# 6_Interfaces.net
KiCad netlist of a schematic drawn in Altium Designer
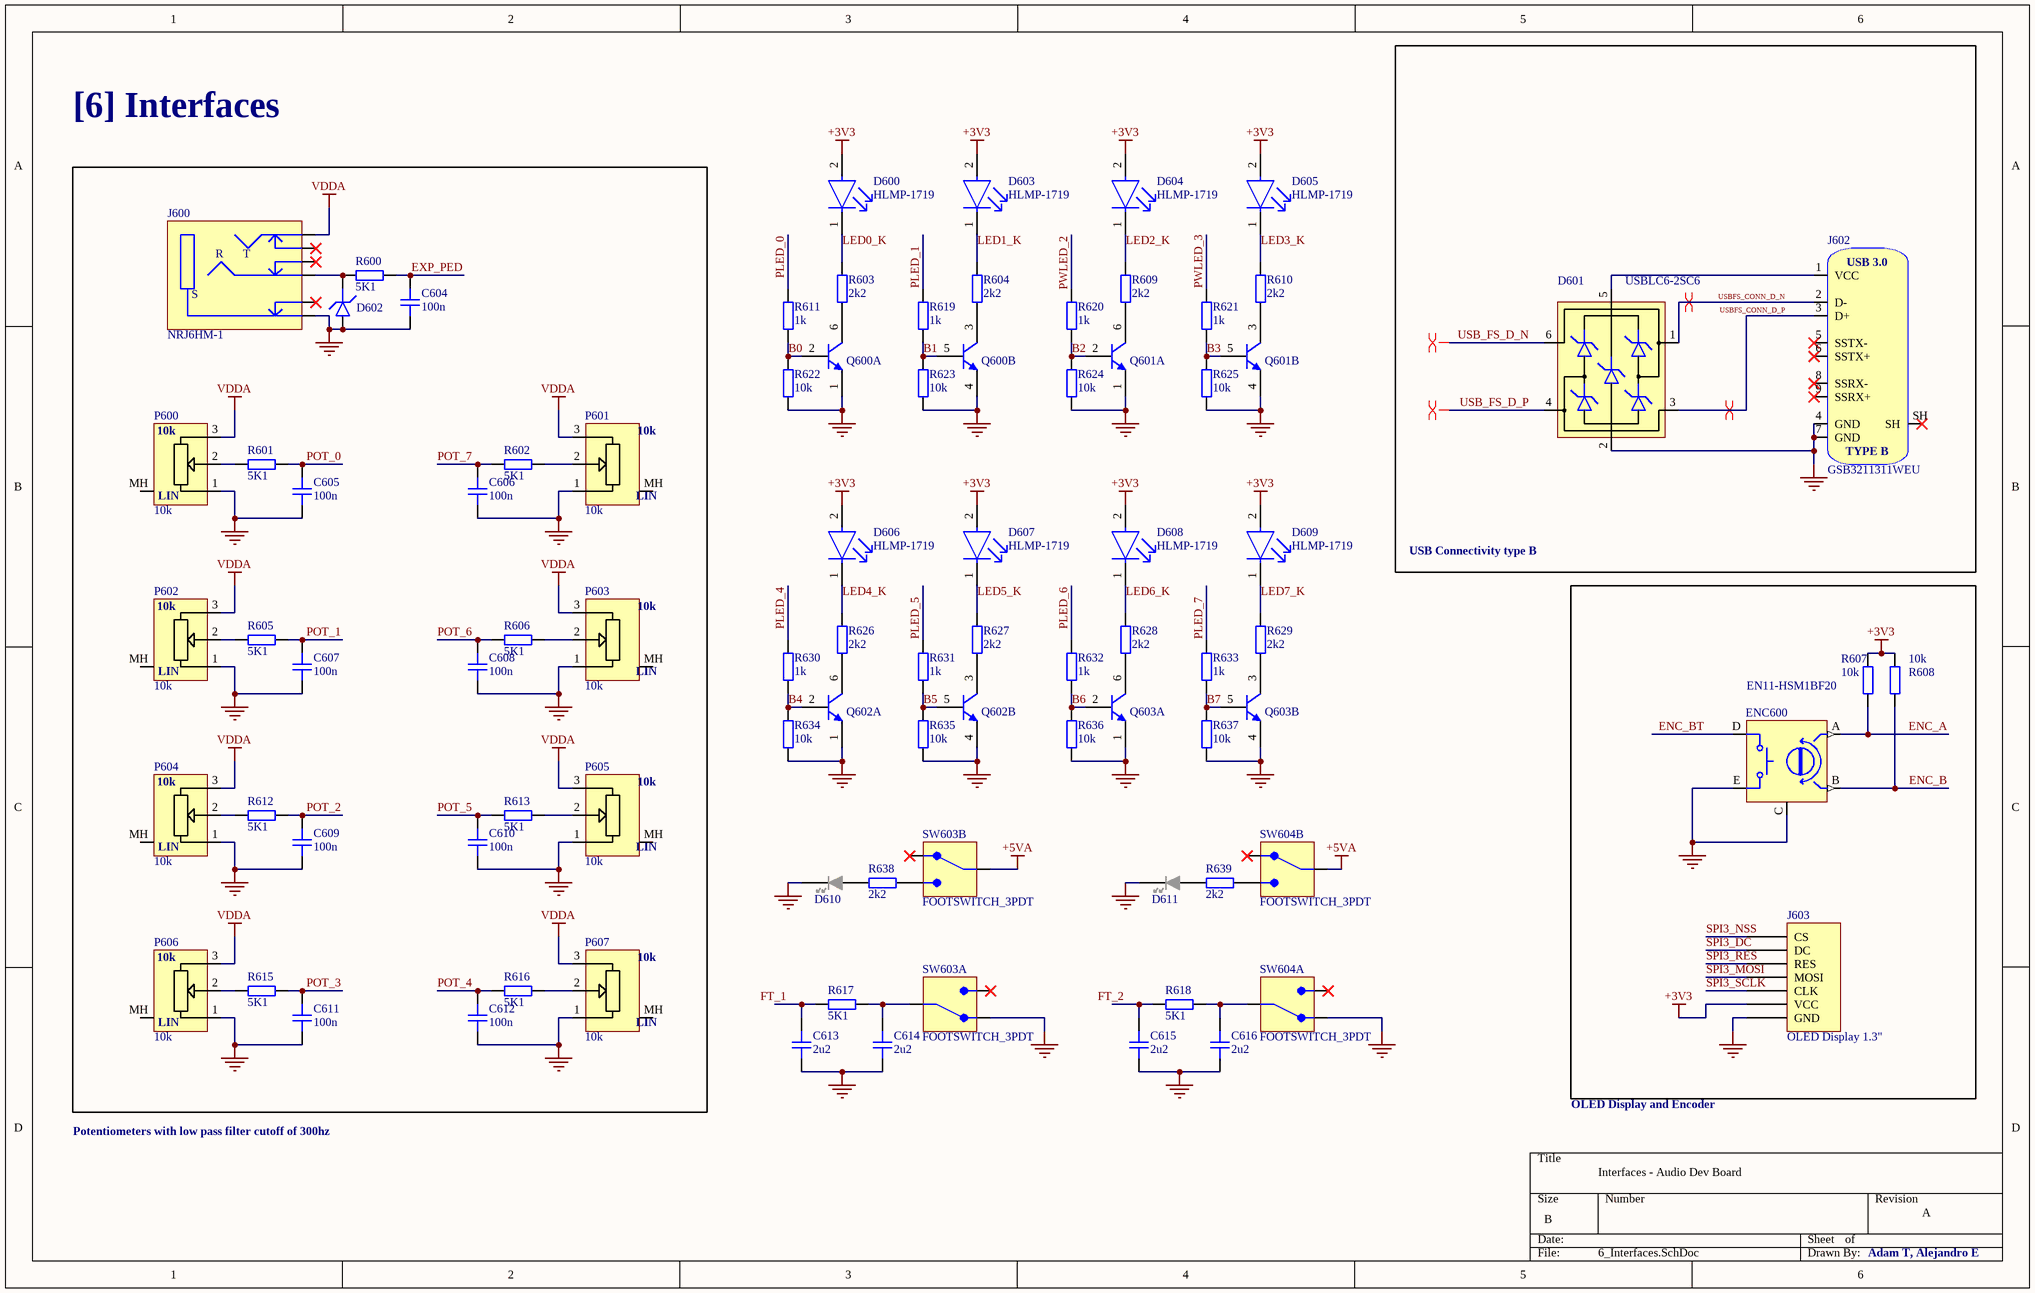
[diagram p0: 6_Interfaces.SchDoc]

(export (version "E")
  (design (tool "Eeschema 10.0.6"))
  (components
    (comp (ref "C604")
      (value "100n")
      (footprint "CAP_0402")
      (description "Capacitor SMD 0402")
      (libsource (lib "Schematic-Lib-PhilsLab") (part "CAP_0402"))
    )
    (comp (ref "C605")
      (value "100n")
      (footprint "CAP_0402")
      (description "Capacitor SMD 0402")
      (libsource (lib "Schematic-Lib-PhilsLab") (part "CAP_0402"))
    )
    (comp (ref "C606")
      (value "100n")
      (footprint "CAP_0402")
      (description "Capacitor SMD 0402")
      (libsource (lib "Schematic-Lib-PhilsLab") (part "CAP_0402"))
    )
    (comp (ref "C607")
      (value "100n")
      (footprint "CAP_0402")
      (description "Capacitor SMD 0402")
      (libsource (lib "Schematic-Lib-PhilsLab") (part "CAP_0402"))
    )
    (comp (ref "C608")
      (value "100n")
      (footprint "CAP_0402")
      (description "Capacitor SMD 0402")
      (libsource (lib "Schematic-Lib-PhilsLab") (part "CAP_0402"))
    )
    (comp (ref "C609")
      (value "100n")
      (footprint "CAP_0402")
      (description "Capacitor SMD 0402")
      (libsource (lib "Schematic-Lib-PhilsLab") (part "CAP_0402"))
    )
    (comp (ref "C610")
      (value "100n")
      (footprint "CAP_0402")
      (description "Capacitor SMD 0402")
      (libsource (lib "Schematic-Lib-PhilsLab") (part "CAP_0402"))
    )
    (comp (ref "C611")
      (value "100n")
      (footprint "CAP_0402")
      (description "Capacitor SMD 0402")
      (libsource (lib "Schematic-Lib-PhilsLab") (part "CAP_0402"))
    )
    (comp (ref "C612")
      (value "100n")
      (footprint "CAP_0402")
      (description "Capacitor SMD 0402")
      (libsource (lib "Schematic-Lib-PhilsLab") (part "CAP_0402"))
    )
    (comp (ref "C613")
      (value "2u2")
      (footprint "CAP_0402")
      (description "Capacitor SMD 0402")
      (libsource (lib "Schematic-Lib-PhilsLab") (part "CAP_0402"))
    )
    (comp (ref "C614")
      (value "2u2")
      (footprint "CAP_0402")
      (description "Capacitor SMD 0402")
      (libsource (lib "Schematic-Lib-PhilsLab") (part "CAP_0402"))
    )
    (comp (ref "C615")
      (value "2u2")
      (footprint "CAP_0402")
      (description "Capacitor SMD 0402")
      (libsource (lib "Schematic-Lib-PhilsLab") (part "CAP_0402"))
    )
    (comp (ref "C616")
      (value "2u2")
      (footprint "CAP_0402")
      (description "Capacitor SMD 0402")
      (libsource (lib "Schematic-Lib-PhilsLab") (part "CAP_0402"))
    )
    (comp (ref "D600")
      (value "HLMP-1719")
      (footprint "FP-HLMP-1719-MFG")
      (description "LED YELLOW DIFFUSED T-1 T/H")
      (fields
        (field (name "MANUFACTURER") "Broadcom")
        (field (name "OCTOPART") "https://octopart.com/hlmp-1719-broadcom-71130405")
      )
      (libsource (lib "Altium Content Vault") (part "8706943c75ba83719d021d2fdc84c58"))
    )
    (comp (ref "D601")
      (value "USBLC6-2SC6")
      (footprint "SOT-23-6")
      (description "Low-Capacitance ESD Protection USB")
      (fields (field (name "MANUFACTURER") "STMicroelectronics"))
      (libsource (lib "Schematic-Lib-PhilsLab") (part "USBLC6-2SC6"))
    )
    (comp (ref "D602")
      (value "CG0402MLU-12G")
      (footprint "D_0402")
      (description "Diode TVS / ESD 0402")
      (libsource (lib "Schematic-Lib-PhilsLab") (part "D_TVS_0402"))
    )
    (comp (ref "D603")
      (value "HLMP-1719")
      (footprint "FP-HLMP-1719-MFG")
      (description "LED YELLOW DIFFUSED T-1 T/H")
      (fields
        (field (name "MANUFACTURER") "Broadcom")
        (field (name "OCTOPART") "https://octopart.com/hlmp-1719-broadcom-71130405")
      )
      (libsource (lib "Altium Content Vault") (part "8706943c75ba83719d021d2fdc84c58"))
    )
    (comp (ref "D604")
      (value "HLMP-1719")
      (footprint "FP-HLMP-1719-MFG")
      (description "LED YELLOW DIFFUSED T-1 T/H")
      (fields
        (field (name "MANUFACTURER") "Broadcom")
        (field (name "OCTOPART") "https://octopart.com/hlmp-1719-broadcom-71130405")
      )
      (libsource (lib "Altium Content Vault") (part "8706943c75ba83719d021d2fdc84c58"))
    )
    (comp (ref "D605")
      (value "HLMP-1719")
      (footprint "FP-HLMP-1719-MFG")
      (description "LED YELLOW DIFFUSED T-1 T/H")
      (fields
        (field (name "MANUFACTURER") "Broadcom")
        (field (name "OCTOPART") "https://octopart.com/hlmp-1719-broadcom-71130405")
      )
      (libsource (lib "Altium Content Vault") (part "8706943c75ba83719d021d2fdc84c58"))
    )
    (comp (ref "D606")
      (value "HLMP-1719")
      (footprint "FP-HLMP-1719-MFG")
      (description "LED YELLOW DIFFUSED T-1 T/H")
      (fields
        (field (name "MANUFACTURER") "Broadcom")
        (field (name "OCTOPART") "https://octopart.com/hlmp-1719-broadcom-71130405")
      )
      (libsource (lib "Altium Content Vault") (part "8706943c75ba83719d021d2fdc84c58"))
    )
    (comp (ref "D607")
      (value "HLMP-1719")
      (footprint "FP-HLMP-1719-MFG")
      (description "LED YELLOW DIFFUSED T-1 T/H")
      (fields
        (field (name "MANUFACTURER") "Broadcom")
        (field (name "OCTOPART") "https://octopart.com/hlmp-1719-broadcom-71130405")
      )
      (libsource (lib "Altium Content Vault") (part "8706943c75ba83719d021d2fdc84c58"))
    )
    (comp (ref "D608")
      (value "HLMP-1719")
      (footprint "FP-HLMP-1719-MFG")
      (description "LED YELLOW DIFFUSED T-1 T/H")
      (fields
        (field (name "MANUFACTURER") "Broadcom")
        (field (name "OCTOPART") "https://octopart.com/hlmp-1719-broadcom-71130405")
      )
      (libsource (lib "Altium Content Vault") (part "8706943c75ba83719d021d2fdc84c58"))
    )
    (comp (ref "D609")
      (value "HLMP-1719")
      (footprint "FP-HLMP-1719-MFG")
      (description "LED YELLOW DIFFUSED T-1 T/H")
      (fields
        (field (name "MANUFACTURER") "Broadcom")
        (field (name "OCTOPART") "https://octopart.com/hlmp-1719-broadcom-71130405")
      )
      (libsource (lib "Altium Content Vault") (part "8706943c75ba83719d021d2fdc84c58"))
    )
    (comp (ref "D610")
      (value "LED")
      (footprint "SLM-530")
      (description "5mm LED Holder Height 17.1mm (w/o LED)")
      (fields (field (name "MANUFACTURER") "BIVAR") (field (name "MANUFACTURER PART NUMBER") "SLM-530"))
      (libsource (lib "Schematic-Lib-PhilsLab") (part "LED_5MM_HOLDER_17MM1"))
    )
    (comp (ref "D611")
      (value "LED")
      (footprint "SLM-530")
      (description "5mm LED Holder Height 17.1mm (w/o LED)")
      (fields (field (name "MANUFACTURER") "BIVAR") (field (name "MANUFACTURER PART NUMBER") "SLM-530"))
      (libsource (lib "Schematic-Lib-PhilsLab") (part "LED_5MM_HOLDER_17MM1"))
    )
    (comp (ref "ENC600")
      (value "EN11-HSM1BF20")
      (footprint "EN11-HSM")
      (description "Rotary Encoder with Switch 20 Detents 7mm Bushing 20mm Threaded Shaft Vertical")
      (fields (field (name "MANUFACTURER") "TT Electronics"))
      (libsource (lib "Schematic-Lib-PhilsLab") (part "EN11-HSM1BF20"))
    )
    (comp (ref "J600")
      (value "NRJ6HM-1")
      (footprint "NRJ6HM-1")
      (description "1/4\" Stereo Jack, TRS Switched")
      (fields (field (name "MANUFACTURER") "Neutrik"))
      (libsource (lib "Schematic-Lib-PhilsLab") (part "NRJ6HM-1"))
    )
    (comp (ref "J602")
      (value "GSB3211311WEU")
      (footprint "GSB3211311WEU")
      (description "USB Connector Type B 3.0 Through-Hole")
      (fields (field (name "MANUFACTURER") "Amphenol"))
      (libsource (lib "Schematic-Lib-PhilsLab") (part "GSB3211311WEU"))
    )
    (comp (ref "J603")
      (value "OLED Display 1.3\"")
      (footprint "OLED Display: 128x64, 1.3\",")
      (description "Poulolu OLED Display: 128x64, 1.3\",")
      (libsource (lib "Schematic-Lib-PhilsLab") (part "OLED Display{colon} 128x64, 1.3{dblquote},"))
    )
    (comp (ref "P600")
      (value "10k")
      (footprint "P0915N-EC15BR10K")
      (description "Potentiometer Vertical 10k Linear Taper THT PCB-Mount Smooth Shaft w/ Slot D=6mm L=15mm")
      (fields
        (field (name "MANUFACTURER") "TT Electronics")
        (field (name "MANUFACTURER PART NUMBER") "P0915N-EC15BR10K")
      )
      (libsource (lib "Schematic-Lib-PhilsLab") (part "P0915N-EC15BR10K"))
    )
    (comp (ref "P601")
      (value "10k")
      (footprint "P0915N-EC15BR10K")
      (description "Potentiometer Vertical 10k Linear Taper THT PCB-Mount Smooth Shaft w/ Slot D=6mm L=15mm")
      (fields
        (field (name "MANUFACTURER") "TT Electronics")
        (field (name "MANUFACTURER PART NUMBER") "P0915N-EC15BR10K")
      )
      (libsource (lib "") (part "P0915N-EC15BR10K_1"))
    )
    (comp (ref "P602")
      (value "10k")
      (footprint "P0915N-EC15BR10K")
      (description "Potentiometer Vertical 10k Linear Taper THT PCB-Mount Smooth Shaft w/ Slot D=6mm L=15mm")
      (fields
        (field (name "MANUFACTURER") "TT Electronics")
        (field (name "MANUFACTURER PART NUMBER") "P0915N-EC15BR10K")
      )
      (libsource (lib "Schematic-Lib-PhilsLab") (part "P0915N-EC15BR10K"))
    )
    (comp (ref "P603")
      (value "10k")
      (footprint "P0915N-EC15BR10K")
      (description "Potentiometer Vertical 10k Linear Taper THT PCB-Mount Smooth Shaft w/ Slot D=6mm L=15mm")
      (fields
        (field (name "MANUFACTURER") "TT Electronics")
        (field (name "MANUFACTURER PART NUMBER") "P0915N-EC15BR10K")
      )
      (libsource (lib "") (part "P0915N-EC15BR10K_1"))
    )
    (comp (ref "P604")
      (value "10k")
      (footprint "P0915N-EC15BR10K")
      (description "Potentiometer Vertical 10k Linear Taper THT PCB-Mount Smooth Shaft w/ Slot D=6mm L=15mm")
      (fields
        (field (name "MANUFACTURER") "TT Electronics")
        (field (name "MANUFACTURER PART NUMBER") "P0915N-EC15BR10K")
      )
      (libsource (lib "Schematic-Lib-PhilsLab") (part "P0915N-EC15BR10K"))
    )
    (comp (ref "P605")
      (value "10k")
      (footprint "P0915N-EC15BR10K")
      (description "Potentiometer Vertical 10k Linear Taper THT PCB-Mount Smooth Shaft w/ Slot D=6mm L=15mm")
      (fields
        (field (name "MANUFACTURER") "TT Electronics")
        (field (name "MANUFACTURER PART NUMBER") "P0915N-EC15BR10K")
      )
      (libsource (lib "") (part "P0915N-EC15BR10K_1"))
    )
    (comp (ref "P606")
      (value "10k")
      (footprint "P0915N-EC15BR10K")
      (description "Potentiometer Vertical 10k Linear Taper THT PCB-Mount Smooth Shaft w/ Slot D=6mm L=15mm")
      (fields
        (field (name "MANUFACTURER") "TT Electronics")
        (field (name "MANUFACTURER PART NUMBER") "P0915N-EC15BR10K")
      )
      (libsource (lib "Schematic-Lib-PhilsLab") (part "P0915N-EC15BR10K"))
    )
    (comp (ref "P607")
      (value "10k")
      (footprint "P0915N-EC15BR10K")
      (description "Potentiometer Vertical 10k Linear Taper THT PCB-Mount Smooth Shaft w/ Slot D=6mm L=15mm")
      (fields
        (field (name "MANUFACTURER") "TT Electronics")
        (field (name "MANUFACTURER PART NUMBER") "P0915N-EC15BR10K")
      )
      (libsource (lib "") (part "P0915N-EC15BR10K_1"))
    )
    (comp (ref "Q600")
      (value "MBT3904DW1T1G")
      (footprint "ONSC-SOT-363-6-419B-02_W_V")
      (description "Dual General Purpose Transistors, 6-Pin SOT-363, Pb-Free, Tape and Reel")
      (fields (field (name "MANUFACTURER") "On Semiconductor"))
      (libsource (lib "Altium Content Vault") (part "ONSC-NPN_NPN-6_F"))
    )
    (comp (ref "Q601")
      (value "MBT3904DW1T1G")
      (footprint "ONSC-SOT-363-6-419B-02_W_V")
      (description "Dual General Purpose Transistors, 6-Pin SOT-363, Pb-Free, Tape and Reel")
      (fields (field (name "MANUFACTURER") "On Semiconductor"))
      (libsource (lib "Altium Content Vault") (part "ONSC-NPN_NPN-6_F"))
    )
    (comp (ref "Q602")
      (value "MBT3904DW1T1G")
      (footprint "ONSC-SOT-363-6-419B-02_W_V")
      (description "Dual General Purpose Transistors, 6-Pin SOT-363, Pb-Free, Tape and Reel")
      (fields (field (name "MANUFACTURER") "On Semiconductor"))
      (libsource (lib "Altium Content Vault") (part "ONSC-NPN_NPN-6_F"))
    )
    (comp (ref "Q603")
      (value "MBT3904DW1T1G")
      (footprint "ONSC-SOT-363-6-419B-02_W_V")
      (description "Dual General Purpose Transistors, 6-Pin SOT-363, Pb-Free, Tape and Reel")
      (fields (field (name "MANUFACTURER") "On Semiconductor"))
      (libsource (lib "Altium Content Vault") (part "ONSC-NPN_NPN-6_F"))
    )
    (comp (ref "R600")
      (value "5K1")
      (footprint "RES_0402")
      (description "Resistor SMD 0402")
      (libsource (lib "Schematic-Lib-PhilsLab") (part "RES_0402"))
    )
    (comp (ref "R601")
      (value "5K1")
      (footprint "RES_0402")
      (description "Resistor SMD 0402")
      (libsource (lib "Schematic-Lib-PhilsLab") (part "RES_0402"))
    )
    (comp (ref "R602")
      (value "5K1")
      (footprint "RES_0402")
      (description "Resistor SMD 0402")
      (libsource (lib "Schematic-Lib-PhilsLab") (part "RES_0402"))
    )
    (comp (ref "R603")
      (value "2k2")
      (footprint "RES_0402")
      (description "Resistor SMD 0402")
      (libsource (lib "Schematic-Lib-PhilsLab") (part "RES_0402"))
    )
    (comp (ref "R604")
      (value "2k2")
      (footprint "RES_0402")
      (description "Resistor SMD 0402")
      (libsource (lib "Schematic-Lib-PhilsLab") (part "RES_0402"))
    )
    (comp (ref "R605")
      (value "5K1")
      (footprint "RES_0402")
      (description "Resistor SMD 0402")
      (libsource (lib "Schematic-Lib-PhilsLab") (part "RES_0402"))
    )
    (comp (ref "R606")
      (value "5K1")
      (footprint "RES_0402")
      (description "Resistor SMD 0402")
      (libsource (lib "Schematic-Lib-PhilsLab") (part "RES_0402"))
    )
    (comp (ref "R607")
      (value "10k")
      (footprint "RES_0402")
      (description "Resistor SMD 0402")
      (libsource (lib "Schematic-Lib-PhilsLab") (part "RES_0402"))
    )
    (comp (ref "R608")
      (value "10k")
      (footprint "RES_0402")
      (description "Resistor SMD 0402")
      (libsource (lib "Schematic-Lib-PhilsLab") (part "RES_0402"))
    )
    (comp (ref "R609")
      (value "2k2")
      (footprint "RES_0402")
      (description "Resistor SMD 0402")
      (libsource (lib "Schematic-Lib-PhilsLab") (part "RES_0402"))
    )
    (comp (ref "R610")
      (value "2k2")
      (footprint "RES_0402")
      (description "Resistor SMD 0402")
      (libsource (lib "Schematic-Lib-PhilsLab") (part "RES_0402"))
    )
    (comp (ref "R611")
      (value "1k")
      (footprint "RES_0402")
      (description "Resistor SMD 0402")
      (libsource (lib "Schematic-Lib-PhilsLab") (part "RES_0402"))
    )
    (comp (ref "R612")
      (value "5K1")
      (footprint "RES_0402")
      (description "Resistor SMD 0402")
      (libsource (lib "Schematic-Lib-PhilsLab") (part "RES_0402"))
    )
    (comp (ref "R613")
      (value "5K1")
      (footprint "RES_0402")
      (description "Resistor SMD 0402")
      (libsource (lib "Schematic-Lib-PhilsLab") (part "RES_0402"))
    )
    (comp (ref "R615")
      (value "5K1")
      (footprint "RES_0402")
      (description "Resistor SMD 0402")
      (libsource (lib "Schematic-Lib-PhilsLab") (part "RES_0402"))
    )
    (comp (ref "R616")
      (value "5K1")
      (footprint "RES_0402")
      (description "Resistor SMD 0402")
      (libsource (lib "Schematic-Lib-PhilsLab") (part "RES_0402"))
    )
    (comp (ref "R617")
      (value "5K1")
      (footprint "RES_0402")
      (description "Resistor SMD 0402")
      (libsource (lib "Schematic-Lib-PhilsLab") (part "RES_0402"))
    )
    (comp (ref "R618")
      (value "5K1")
      (footprint "RES_0402")
      (description "Resistor SMD 0402")
      (libsource (lib "Schematic-Lib-PhilsLab") (part "RES_0402"))
    )
    (comp (ref "R619")
      (value "1k")
      (footprint "RES_0402")
      (description "Resistor SMD 0402")
      (libsource (lib "Schematic-Lib-PhilsLab") (part "RES_0402"))
    )
    (comp (ref "R620")
      (value "1k")
      (footprint "RES_0402")
      (description "Resistor SMD 0402")
      (libsource (lib "Schematic-Lib-PhilsLab") (part "RES_0402"))
    )
    (comp (ref "R621")
      (value "1k")
      (footprint "RES_0402")
      (description "Resistor SMD 0402")
      (libsource (lib "Schematic-Lib-PhilsLab") (part "RES_0402"))
    )
    (comp (ref "R622")
      (value "10k")
      (footprint "RES_0402")
      (description "Resistor SMD 0402")
      (libsource (lib "Schematic-Lib-PhilsLab") (part "RES_0402"))
    )
    (comp (ref "R623")
      (value "10k")
      (footprint "RES_0402")
      (description "Resistor SMD 0402")
      (libsource (lib "Schematic-Lib-PhilsLab") (part "RES_0402"))
    )
    (comp (ref "R624")
      (value "10k")
      (footprint "RES_0402")
      (description "Resistor SMD 0402")
      (libsource (lib "Schematic-Lib-PhilsLab") (part "RES_0402"))
    )
    (comp (ref "R625")
      (value "10k")
      (footprint "RES_0402")
      (description "Resistor SMD 0402")
      (libsource (lib "Schematic-Lib-PhilsLab") (part "RES_0402"))
    )
    (comp (ref "R626")
      (value "2k2")
      (footprint "RES_0402")
      (description "Resistor SMD 0402")
      (libsource (lib "Schematic-Lib-PhilsLab") (part "RES_0402"))
    )
    (comp (ref "R627")
      (value "2k2")
      (footprint "RES_0402")
      (description "Resistor SMD 0402")
      (libsource (lib "Schematic-Lib-PhilsLab") (part "RES_0402"))
    )
    (comp (ref "R628")
      (value "2k2")
      (footprint "RES_0402")
      (description "Resistor SMD 0402")
      (libsource (lib "Schematic-Lib-PhilsLab") (part "RES_0402"))
    )
    (comp (ref "R629")
      (value "2k2")
      (footprint "RES_0402")
      (description "Resistor SMD 0402")
      (libsource (lib "Schematic-Lib-PhilsLab") (part "RES_0402"))
    )
    (comp (ref "R630")
      (value "1k")
      (footprint "RES_0402")
      (description "Resistor SMD 0402")
      (libsource (lib "Schematic-Lib-PhilsLab") (part "RES_0402"))
    )
    (comp (ref "R631")
      (value "1k")
      (footprint "RES_0402")
      (description "Resistor SMD 0402")
      (libsource (lib "Schematic-Lib-PhilsLab") (part "RES_0402"))
    )
    (comp (ref "R632")
      (value "1k")
      (footprint "RES_0402")
      (description "Resistor SMD 0402")
      (libsource (lib "Schematic-Lib-PhilsLab") (part "RES_0402"))
    )
    (comp (ref "R633")
      (value "1k")
      (footprint "RES_0402")
      (description "Resistor SMD 0402")
      (libsource (lib "Schematic-Lib-PhilsLab") (part "RES_0402"))
    )
    (comp (ref "R634")
      (value "10k")
      (footprint "RES_0402")
      (description "Resistor SMD 0402")
      (libsource (lib "Schematic-Lib-PhilsLab") (part "RES_0402"))
    )
    (comp (ref "R635")
      (value "10k")
      (footprint "RES_0402")
      (description "Resistor SMD 0402")
      (libsource (lib "Schematic-Lib-PhilsLab") (part "RES_0402"))
    )
    (comp (ref "R636")
      (value "10k")
      (footprint "RES_0402")
      (description "Resistor SMD 0402")
      (libsource (lib "Schematic-Lib-PhilsLab") (part "RES_0402"))
    )
    (comp (ref "R637")
      (value "10k")
      (footprint "RES_0402")
      (description "Resistor SMD 0402")
      (libsource (lib "Schematic-Lib-PhilsLab") (part "RES_0402"))
    )
    (comp (ref "R638")
      (value "2k2")
      (footprint "RES_0402")
      (description "Resistor SMD 0402")
      (libsource (lib "Schematic-Lib-PhilsLab") (part "RES_0402"))
    )
    (comp (ref "R639")
      (value "2k2")
      (footprint "RES_0402")
      (description "Resistor SMD 0402")
      (libsource (lib "Schematic-Lib-PhilsLab") (part "RES_0402"))
    )
    (comp (ref "SW603")
      (value "FOOTSWITCH_3PDT")
      (footprint "FOOTSWITCH_3PDT")
      (description "Generic 3PDT Footswitch")
      (libsource (lib "") (part "FOOTSWITCH_3PDT_1"))
    )
    (comp (ref "SW604")
      (value "FOOTSWITCH_3PDT")
      (footprint "FOOTSWITCH_3PDT")
      (description "Generic 3PDT Footswitch")
      (libsource (lib "") (part "FOOTSWITCH_3PDT_1"))
    )
  )
  (nets
    (net (code "1") (name "+3V3") (class "Default")
      (node (ref "D600") (pin "2") (pinfunction "A_2") (pintype "passive"))
      (node (ref "D603") (pin "2") (pinfunction "A_2") (pintype "passive"))
      (node (ref "D604") (pin "2") (pinfunction "A_2") (pintype "passive"))
      (node (ref "D605") (pin "2") (pinfunction "A_2") (pintype "passive"))
      (node (ref "D606") (pin "2") (pinfunction "A_2") (pintype "passive"))
      (node (ref "D607") (pin "2") (pinfunction "A_2") (pintype "passive"))
      (node (ref "D608") (pin "2") (pinfunction "A_2") (pintype "passive"))
      (node (ref "D609") (pin "2") (pinfunction "A_2") (pintype "passive"))
      (node (ref "J603") (pin "VCC") (pinfunction "VCC_VCC") (pintype "passive"))
      (node (ref "R607") (pin "2") (pinfunction "2_2") (pintype "passive"))
      (node (ref "R608") (pin "2") (pinfunction "2_2") (pintype "passive"))
    )
    (net (code "2") (name "+5VA") (class "Default")
      (node (ref "SW603") (pin "COM2") (pinfunction "COM2_COM2") (pintype "passive"))
      (node (ref "SW604") (pin "COM2") (pinfunction "COM2_COM2") (pintype "passive"))
    )
    (net (code "3") (name "/B0") (class "Default")
      (node (ref "Q600") (pin "2") (pinfunction "B_2") (pintype "passive"))
      (node (ref "R611") (pin "1") (pinfunction "1_1") (pintype "passive"))
      (node (ref "R622") (pin "2") (pinfunction "2_2") (pintype "passive"))
    )
    (net (code "4") (name "/B1") (class "Default")
      (node (ref "Q600") (pin "5") (pinfunction "B_5") (pintype "passive"))
      (node (ref "R619") (pin "1") (pinfunction "1_1") (pintype "passive"))
      (node (ref "R623") (pin "2") (pinfunction "2_2") (pintype "passive"))
    )
    (net (code "5") (name "/B2") (class "Default")
      (node (ref "Q601") (pin "2") (pinfunction "B_2") (pintype "passive"))
      (node (ref "R620") (pin "1") (pinfunction "1_1") (pintype "passive"))
      (node (ref "R624") (pin "2") (pinfunction "2_2") (pintype "passive"))
    )
    (net (code "6") (name "/B3") (class "Default")
      (node (ref "Q601") (pin "5") (pinfunction "B_5") (pintype "passive"))
      (node (ref "R621") (pin "1") (pinfunction "1_1") (pintype "passive"))
      (node (ref "R625") (pin "2") (pinfunction "2_2") (pintype "passive"))
    )
    (net (code "7") (name "/B4") (class "Default")
      (node (ref "Q602") (pin "2") (pinfunction "B_2") (pintype "passive"))
      (node (ref "R630") (pin "1") (pinfunction "1_1") (pintype "passive"))
      (node (ref "R634") (pin "2") (pinfunction "2_2") (pintype "passive"))
    )
    (net (code "8") (name "/B5") (class "Default")
      (node (ref "Q602") (pin "5") (pinfunction "B_5") (pintype "passive"))
      (node (ref "R631") (pin "1") (pinfunction "1_1") (pintype "passive"))
      (node (ref "R635") (pin "2") (pinfunction "2_2") (pintype "passive"))
    )
    (net (code "9") (name "/B6") (class "Default")
      (node (ref "Q603") (pin "2") (pinfunction "B_2") (pintype "passive"))
      (node (ref "R632") (pin "1") (pinfunction "1_1") (pintype "passive"))
      (node (ref "R636") (pin "2") (pinfunction "2_2") (pintype "passive"))
    )
    (net (code "10") (name "/B7") (class "Default")
      (node (ref "Q603") (pin "5") (pinfunction "B_5") (pintype "passive"))
      (node (ref "R633") (pin "1") (pinfunction "1_1") (pintype "passive"))
      (node (ref "R637") (pin "2") (pinfunction "2_2") (pintype "passive"))
    )
    (net (code "11") (name "/ENC_A") (class "Default")
      (node (ref "ENC600") (pin "A") (pinfunction "A_A") (pintype "output"))
      (node (ref "R607") (pin "1") (pinfunction "1_1") (pintype "passive"))
    )
    (net (code "12") (name "/ENC_B") (class "Default")
      (node (ref "ENC600") (pin "B") (pinfunction "B_B") (pintype "output"))
      (node (ref "R608") (pin "1") (pinfunction "1_1") (pintype "passive"))
    )
    (net (code "13") (name "/ENC_BT") (class "Default")
      (node (ref "ENC600") (pin "D") (pinfunction "D_D") (pintype "passive"))
    )
    (net (code "14") (name "/EXP_PED") (class "Default")
      (node (ref "C604") (pin "2") (pinfunction "2_2") (pintype "passive"))
      (node (ref "R600") (pin "2") (pinfunction "2_2") (pintype "passive"))
    )
    (net (code "15") (name "/FT_1") (class "Default")
      (node (ref "C613") (pin "2") (pinfunction "2_2") (pintype "passive"))
      (node (ref "R617") (pin "1") (pinfunction "1_1") (pintype "passive"))
    )
    (net (code "16") (name "/FT_2") (class "Default")
      (node (ref "C615") (pin "2") (pinfunction "2_2") (pintype "passive"))
      (node (ref "R618") (pin "1") (pinfunction "1_1") (pintype "passive"))
    )
    (net (code "17") (name "/LED0_K") (class "Default")
      (node (ref "D600") (pin "1") (pinfunction "C_1") (pintype "passive"))
      (node (ref "R603") (pin "2") (pinfunction "2_2") (pintype "passive"))
    )
    (net (code "18") (name "/LED1_K") (class "Default")
      (node (ref "D603") (pin "1") (pinfunction "C_1") (pintype "passive"))
      (node (ref "R604") (pin "2") (pinfunction "2_2") (pintype "passive"))
    )
    (net (code "19") (name "/LED2_K") (class "Default")
      (node (ref "D604") (pin "1") (pinfunction "C_1") (pintype "passive"))
      (node (ref "R609") (pin "2") (pinfunction "2_2") (pintype "passive"))
    )
    (net (code "20") (name "/LED3_K") (class "Default")
      (node (ref "D605") (pin "1") (pinfunction "C_1") (pintype "passive"))
      (node (ref "R610") (pin "2") (pinfunction "2_2") (pintype "passive"))
    )
    (net (code "21") (name "/LED4_K") (class "Default")
      (node (ref "D606") (pin "1") (pinfunction "C_1") (pintype "passive"))
      (node (ref "R626") (pin "2") (pinfunction "2_2") (pintype "passive"))
    )
    (net (code "22") (name "/LED5_K") (class "Default")
      (node (ref "D607") (pin "1") (pinfunction "C_1") (pintype "passive"))
      (node (ref "R627") (pin "2") (pinfunction "2_2") (pintype "passive"))
    )
    (net (code "23") (name "/LED6_K") (class "Default")
      (node (ref "D608") (pin "1") (pinfunction "C_1") (pintype "passive"))
      (node (ref "R628") (pin "2") (pinfunction "2_2") (pintype "passive"))
    )
    (net (code "24") (name "/LED7_K") (class "Default")
      (node (ref "D609") (pin "1") (pinfunction "C_1") (pintype "passive"))
      (node (ref "R629") (pin "2") (pinfunction "2_2") (pintype "passive"))
    )
    (net (code "25") (name "/PLED_0") (class "Default")
      (node (ref "R611") (pin "2") (pinfunction "2_2") (pintype "passive"))
    )
    (net (code "26") (name "/PLED_1") (class "Default")
      (node (ref "R619") (pin "2") (pinfunction "2_2") (pintype "passive"))
    )
    (net (code "27") (name "/PLED_4") (class "Default")
      (node (ref "R630") (pin "2") (pinfunction "2_2") (pintype "passive"))
    )
    (net (code "28") (name "/PLED_5") (class "Default")
      (node (ref "R631") (pin "2") (pinfunction "2_2") (pintype "passive"))
    )
    (net (code "29") (name "/PLED_6") (class "Default")
      (node (ref "R632") (pin "2") (pinfunction "2_2") (pintype "passive"))
    )
    (net (code "30") (name "/PLED_7") (class "Default")
      (node (ref "R633") (pin "2") (pinfunction "2_2") (pintype "passive"))
    )
    (net (code "31") (name "/POT_0") (class "Default")
      (node (ref "C605") (pin "2") (pinfunction "2_2") (pintype "passive"))
      (node (ref "R601") (pin "2") (pinfunction "2_2") (pintype "passive"))
    )
    (net (code "32") (name "/POT_1") (class "Default")
      (node (ref "C607") (pin "2") (pinfunction "2_2") (pintype "passive"))
      (node (ref "R605") (pin "2") (pinfunction "2_2") (pintype "passive"))
    )
    (net (code "33") (name "/POT_2") (class "Default")
      (node (ref "C609") (pin "2") (pinfunction "2_2") (pintype "passive"))
      (node (ref "R612") (pin "2") (pinfunction "2_2") (pintype "passive"))
    )
    (net (code "34") (name "/POT_3") (class "Default")
      (node (ref "C611") (pin "2") (pinfunction "2_2") (pintype "passive"))
      (node (ref "R615") (pin "2") (pinfunction "2_2") (pintype "passive"))
    )
    (net (code "35") (name "/POT_4") (class "Default")
      (node (ref "C612") (pin "2") (pinfunction "2_2") (pintype "passive"))
      (node (ref "R616") (pin "1") (pinfunction "1_1") (pintype "passive"))
    )
    (net (code "36") (name "/POT_5") (class "Default")
      (node (ref "C610") (pin "2") (pinfunction "2_2") (pintype "passive"))
      (node (ref "R613") (pin "1") (pinfunction "1_1") (pintype "passive"))
    )
    (net (code "37") (name "/POT_6") (class "Default")
      (node (ref "C608") (pin "2") (pinfunction "2_2") (pintype "passive"))
      (node (ref "R606") (pin "1") (pinfunction "1_1") (pintype "passive"))
    )
    (net (code "38") (name "/POT_7") (class "Default")
      (node (ref "C606") (pin "2") (pinfunction "2_2") (pintype "passive"))
      (node (ref "R602") (pin "1") (pinfunction "1_1") (pintype "passive"))
    )
    (net (code "39") (name "/PWLED_2") (class "Default")
      (node (ref "R620") (pin "2") (pinfunction "2_2") (pintype "passive"))
    )
    (net (code "40") (name "/PWLED_3") (class "Default")
      (node (ref "R621") (pin "2") (pinfunction "2_2") (pintype "passive"))
    )
    (net (code "41") (name "/SPI3_DC") (class "Default")
      (node (ref "J603") (pin "DC") (pinfunction "DC_DC") (pintype "passive"))
    )
    (net (code "42") (name "/SPI3_MOSI") (class "Default")
      (node (ref "J603") (pin "MOSI") (pinfunction "MOSI_MOSI") (pintype "passive"))
    )
    (net (code "43") (name "/SPI3_NSS") (class "Default")
      (node (ref "J603") (pin "CS") (pinfunction "CS_CS") (pintype "passive"))
    )
    (net (code "44") (name "/SPI3_RES") (class "Default")
      (node (ref "J603") (pin "RES") (pinfunction "RES_RES") (pintype "passive"))
    )
    (net (code "45") (name "/SPI3_SCLK") (class "Default")
      (node (ref "J603") (pin "CLK") (pinfunction "CLK_CLK") (pintype "passive"))
    )
    (net (code "46") (name "/USBFS_CONN_D_N") (class "Default")
      (node (ref "D601") (pin "1") (pinfunction "IO1_1") (pintype "bidirectional"))
      (node (ref "J602") (pin "2") (pinfunction "D-_2") (pintype "passive"))
    )
    (net (code "47") (name "/USBFS_CONN_D_P") (class "Default")
      (node (ref "D601") (pin "3") (pinfunction "IO2_3") (pintype "bidirectional"))
      (node (ref "J602") (pin "3") (pinfunction "D+_3") (pintype "passive"))
    )
    (net (code "48") (name "/USB_FS_D_N") (class "Default")
      (node (ref "D601") (pin "6") (pinfunction "IO1_6") (pintype "bidirectional"))
    )
    (net (code "49") (name "/USB_FS_D_P") (class "Default")
      (node (ref "D601") (pin "4") (pinfunction "IO2_4") (pintype "bidirectional"))
    )
    (net (code "50") (name "GND") (class "Default")
      (node (ref "C604") (pin "1") (pinfunction "1_1") (pintype "passive"))
      (node (ref "C605") (pin "1") (pinfunction "1_1") (pintype "passive"))
      (node (ref "C606") (pin "1") (pinfunction "1_1") (pintype "passive"))
      (node (ref "C607") (pin "1") (pinfunction "1_1") (pintype "passive"))
      (node (ref "C608") (pin "1") (pinfunction "1_1") (pintype "passive"))
      (node (ref "C609") (pin "1") (pinfunction "1_1") (pintype "passive"))
      (node (ref "C610") (pin "1") (pinfunction "1_1") (pintype "passive"))
      (node (ref "C611") (pin "1") (pinfunction "1_1") (pintype "passive"))
      (node (ref "C612") (pin "1") (pinfunction "1_1") (pintype "passive"))
      (node (ref "C613") (pin "1") (pinfunction "1_1") (pintype "passive"))
      (node (ref "C614") (pin "1") (pinfunction "1_1") (pintype "passive"))
      (node (ref "C615") (pin "1") (pinfunction "1_1") (pintype "passive"))
      (node (ref "C616") (pin "1") (pinfunction "1_1") (pintype "passive"))
      (node (ref "D601") (pin "2") (pinfunction "GND_2") (pintype "power_in"))
      (node (ref "D602") (pin "A") (pinfunction "A_A") (pintype "passive"))
      (node (ref "D610") (pin "K") (pinfunction "K_K") (pintype "passive"))
      (node (ref "D611") (pin "K") (pinfunction "K_K") (pintype "passive"))
      (node (ref "ENC600") (pin "C") (pinfunction "GND_C") (pintype "power_in"))
      (node (ref "ENC600") (pin "E") (pinfunction "E_E") (pintype "passive"))
      (node (ref "J600") (pin "S") (pinfunction "S_S") (pintype "passive"))
      (node (ref "J602") (pin "4") (pinfunction "GND_4") (pintype "passive"))
      (node (ref "J602") (pin "7") (pinfunction "GND_7") (pintype "passive"))
      (node (ref "J603") (pin "Gnd") (pinfunction "GND_Gnd") (pintype "passive"))
      (node (ref "P600") (pin "1") (pinfunction "1_1") (pintype "passive"))
      (node (ref "P601") (pin "1") (pinfunction "1_1") (pintype "passive"))
      (node (ref "P602") (pin "1") (pinfunction "1_1") (pintype "passive"))
      (node (ref "P603") (pin "1") (pinfunction "1_1") (pintype "passive"))
      (node (ref "P604") (pin "1") (pinfunction "1_1") (pintype "passive"))
      (node (ref "P605") (pin "1") (pinfunction "1_1") (pintype "passive"))
      (node (ref "P606") (pin "1") (pinfunction "1_1") (pintype "passive"))
      (node (ref "P607") (pin "1") (pinfunction "1_1") (pintype "passive"))
      (node (ref "Q600") (pin "1") (pinfunction "E_1") (pintype "passive"))
      (node (ref "Q600") (pin "4") (pinfunction "E_4") (pintype "passive"))
      (node (ref "Q601") (pin "1") (pinfunction "E_1") (pintype "passive"))
      (node (ref "Q601") (pin "4") (pinfunction "E_4") (pintype "passive"))
      (node (ref "Q602") (pin "1") (pinfunction "E_1") (pintype "passive"))
      (node (ref "Q602") (pin "4") (pinfunction "E_4") (pintype "passive"))
      (node (ref "Q603") (pin "1") (pinfunction "E_1") (pintype "passive"))
      (node (ref "Q603") (pin "4") (pinfunction "E_4") (pintype "passive"))
      (node (ref "R622") (pin "1") (pinfunction "1_1") (pintype "passive"))
      (node (ref "R623") (pin "1") (pinfunction "1_1") (pintype "passive"))
      (node (ref "R624") (pin "1") (pinfunction "1_1") (pintype "passive"))
      (node (ref "R625") (pin "1") (pinfunction "1_1") (pintype "passive"))
      (node (ref "R634") (pin "1") (pinfunction "1_1") (pintype "passive"))
      (node (ref "R635") (pin "1") (pinfunction "1_1") (pintype "passive"))
      (node (ref "R636") (pin "1") (pinfunction "1_1") (pintype "passive"))
      (node (ref "R637") (pin "1") (pinfunction "1_1") (pintype "passive"))
      (node (ref "SW603") (pin "NC1") (pinfunction "NC1_NC1") (pintype "passive"))
      (node (ref "SW604") (pin "NC1") (pinfunction "NC1_NC1") (pintype "passive"))
    )
    (net (code "51") (name "Net-(C614-Pad2)") (class "Default")
      (node (ref "C614") (pin "2") (pinfunction "2_2") (pintype "passive"))
      (node (ref "R617") (pin "2") (pinfunction "2_2") (pintype "passive"))
      (node (ref "SW603") (pin "COM1") (pinfunction "COM1_COM1") (pintype "passive"))
    )
    (net (code "52") (name "Net-(C616-Pad2)") (class "Default")
      (node (ref "C616") (pin "2") (pinfunction "2_2") (pintype "passive"))
      (node (ref "R618") (pin "2") (pinfunction "2_2") (pintype "passive"))
      (node (ref "SW604") (pin "COM1") (pinfunction "COM1_COM1") (pintype "passive"))
    )
    (net (code "53") (name "Net-(D601-VBUS)") (class "Default")
      (node (ref "D601") (pin "5") (pinfunction "VBUS_5") (pintype "power_in"))
      (node (ref "J602") (pin "1") (pinfunction "VCC_1") (pintype "passive"))
    )
    (net (code "54") (name "Net-(D602-PadK)") (class "Default")
      (node (ref "D602") (pin "K") (pinfunction "K_K") (pintype "passive"))
      (node (ref "J600") (pin "R") (pinfunction "R_R") (pintype "passive"))
      (node (ref "R600") (pin "1") (pinfunction "1_1") (pintype "passive"))
    )
    (net (code "55") (name "Net-(D610-PadA)") (class "Default")
      (node (ref "D610") (pin "A") (pinfunction "A_A") (pintype "passive"))
      (node (ref "R638") (pin "2") (pinfunction "2_2") (pintype "passive"))
    )
    (net (code "56") (name "Net-(D611-PadA)") (class "Default")
      (node (ref "D611") (pin "A") (pinfunction "A_A") (pintype "passive"))
      (node (ref "R639") (pin "2") (pinfunction "2_2") (pintype "passive"))
    )
    (net (code "57") (name "Net-(P600-Pad2)") (class "Default")
      (node (ref "P600") (pin "2") (pinfunction "2_2") (pintype "passive"))
      (node (ref "R601") (pin "1") (pinfunction "1_1") (pintype "passive"))
    )
    (net (code "58") (name "Net-(P601-Pad2)") (class "Default")
      (node (ref "P601") (pin "2") (pinfunction "2_2") (pintype "passive"))
      (node (ref "R602") (pin "2") (pinfunction "2_2") (pintype "passive"))
    )
    (net (code "59") (name "Net-(P602-Pad2)") (class "Default")
      (node (ref "P602") (pin "2") (pinfunction "2_2") (pintype "passive"))
      (node (ref "R605") (pin "1") (pinfunction "1_1") (pintype "passive"))
    )
    (net (code "60") (name "Net-(P603-Pad2)") (class "Default")
      (node (ref "P603") (pin "2") (pinfunction "2_2") (pintype "passive"))
      (node (ref "R606") (pin "2") (pinfunction "2_2") (pintype "passive"))
    )
    (net (code "61") (name "Net-(P604-Pad2)") (class "Default")
      (node (ref "P604") (pin "2") (pinfunction "2_2") (pintype "passive"))
      (node (ref "R612") (pin "1") (pinfunction "1_1") (pintype "passive"))
    )
    (net (code "62") (name "Net-(P605-Pad2)") (class "Default")
      (node (ref "P605") (pin "2") (pinfunction "2_2") (pintype "passive"))
      (node (ref "R613") (pin "2") (pinfunction "2_2") (pintype "passive"))
    )
    (net (code "63") (name "Net-(P606-Pad2)") (class "Default")
      (node (ref "P606") (pin "2") (pinfunction "2_2") (pintype "passive"))
      (node (ref "R615") (pin "1") (pinfunction "1_1") (pintype "passive"))
    )
    (net (code "64") (name "Net-(P607-Pad2)") (class "Default")
      (node (ref "P607") (pin "2") (pinfunction "2_2") (pintype "passive"))
      (node (ref "R616") (pin "2") (pinfunction "2_2") (pintype "passive"))
    )
    (net (code "65") (name "Net-(Q600A-C)") (class "Default")
      (node (ref "Q600") (pin "6") (pinfunction "C_6") (pintype "passive"))
      (node (ref "R603") (pin "1") (pinfunction "1_1") (pintype "passive"))
    )
    (net (code "66") (name "Net-(Q600B-C)") (class "Default")
      (node (ref "Q600") (pin "3") (pinfunction "C_3") (pintype "passive"))
      (node (ref "R604") (pin "1") (pinfunction "1_1") (pintype "passive"))
    )
    (net (code "67") (name "Net-(Q601A-C)") (class "Default")
      (node (ref "Q601") (pin "6") (pinfunction "C_6") (pintype "passive"))
      (node (ref "R609") (pin "1") (pinfunction "1_1") (pintype "passive"))
    )
    (net (code "68") (name "Net-(Q601B-C)") (class "Default")
      (node (ref "Q601") (pin "3") (pinfunction "C_3") (pintype "passive"))
      (node (ref "R610") (pin "1") (pinfunction "1_1") (pintype "passive"))
    )
    (net (code "69") (name "Net-(Q602A-C)") (class "Default")
      (node (ref "Q602") (pin "6") (pinfunction "C_6") (pintype "passive"))
      (node (ref "R626") (pin "1") (pinfunction "1_1") (pintype "passive"))
    )
    (net (code "70") (name "Net-(Q602B-C)") (class "Default")
      (node (ref "Q602") (pin "3") (pinfunction "C_3") (pintype "passive"))
      (node (ref "R627") (pin "1") (pinfunction "1_1") (pintype "passive"))
    )
    (net (code "71") (name "Net-(Q603A-C)") (class "Default")
      (node (ref "Q603") (pin "6") (pinfunction "C_6") (pintype "passive"))
      (node (ref "R628") (pin "1") (pinfunction "1_1") (pintype "passive"))
    )
    (net (code "72") (name "Net-(Q603B-C)") (class "Default")
      (node (ref "Q603") (pin "3") (pinfunction "C_3") (pintype "passive"))
      (node (ref "R629") (pin "1") (pinfunction "1_1") (pintype "passive"))
    )
    (net (code "73") (name "Net-(R638-Pad1)") (class "Default")
      (node (ref "R638") (pin "1") (pinfunction "1_1") (pintype "passive"))
      (node (ref "SW603") (pin "NO2") (pinfunction "NO2_NO2") (pintype "passive"))
    )
    (net (code "74") (name "Net-(R639-Pad1)") (class "Default")
      (node (ref "R639") (pin "1") (pinfunction "1_1") (pintype "passive"))
      (node (ref "SW604") (pin "NO2") (pinfunction "NO2_NO2") (pintype "passive"))
    )
    (net (code "75") (name "VDDA") (class "Default")
      (node (ref "J600") (pin "T") (pinfunction "T_T") (pintype "passive"))
      (node (ref "P600") (pin "3") (pinfunction "3_3") (pintype "passive"))
      (node (ref "P601") (pin "3") (pinfunction "3_3") (pintype "passive"))
      (node (ref "P602") (pin "3") (pinfunction "3_3") (pintype "passive"))
      (node (ref "P603") (pin "3") (pinfunction "3_3") (pintype "passive"))
      (node (ref "P604") (pin "3") (pinfunction "3_3") (pintype "passive"))
      (node (ref "P605") (pin "3") (pinfunction "3_3") (pintype "passive"))
      (node (ref "P606") (pin "3") (pinfunction "3_3") (pintype "passive"))
      (node (ref "P607") (pin "3") (pinfunction "3_3") (pintype "passive"))
    )
    (net (code "76") (name "unconnected-(J600-PadRN)") (class "Default")
      (node (ref "J600") (pin "RN") (pinfunction "RN_RN") (pintype "passive+no_connect"))
    )
    (net (code "77") (name "unconnected-(J600-PadSN)") (class "Default")
      (node (ref "J600") (pin "SN") (pinfunction "SN_SN") (pintype "passive+no_connect"))
    )
    (net (code "78") (name "unconnected-(J600-PadTN)") (class "Default")
      (node (ref "J600") (pin "TN") (pinfunction "TN_TN") (pintype "passive+no_connect"))
    )
    (net (code "79") (name "unconnected-(J602-PadSH)") (class "Default")
      (node (ref "J602") (pin "SH") (pinfunction "SH_SH") (pintype "passive+no_connect"))
    )
    (net (code "80") (name "unconnected-(J602-SSRX+-Pad9)") (class "Default")
      (node (ref "J602") (pin "9") (pinfunction "SSRX+_9") (pintype "passive+no_connect"))
    )
    (net (code "81") (name "unconnected-(J602-SSRX--Pad8)") (class "Default")
      (node (ref "J602") (pin "8") (pinfunction "SSRX-_8") (pintype "passive+no_connect"))
    )
    (net (code "82") (name "unconnected-(J602-SSTX+-Pad6)") (class "Default")
      (node (ref "J602") (pin "6") (pinfunction "SSTX+_6") (pintype "passive+no_connect"))
    )
    (net (code "83") (name "unconnected-(J602-SSTX--Pad5)") (class "Default")
      (node (ref "J602") (pin "5") (pinfunction "SSTX-_5") (pintype "passive+no_connect"))
    )
    (net (code "84") (name "unconnected-(P600-PadMH)") (class "Default")
      (node (ref "P600") (pin "MH") (pinfunction "MH_MH") (pintype "passive"))
    )
    (net (code "85") (name "unconnected-(P601-PadMH)") (class "Default")
      (node (ref "P601") (pin "MH") (pinfunction "MH_MH") (pintype "passive"))
    )
    (net (code "86") (name "unconnected-(P602-PadMH)") (class "Default")
      (node (ref "P602") (pin "MH") (pinfunction "MH_MH") (pintype "passive"))
    )
    (net (code "87") (name "unconnected-(P603-PadMH)") (class "Default")
      (node (ref "P603") (pin "MH") (pinfunction "MH_MH") (pintype "passive"))
    )
    (net (code "88") (name "unconnected-(P604-PadMH)") (class "Default")
      (node (ref "P604") (pin "MH") (pinfunction "MH_MH") (pintype "passive"))
    )
    (net (code "89") (name "unconnected-(P605-PadMH)") (class "Default")
      (node (ref "P605") (pin "MH") (pinfunction "MH_MH") (pintype "passive"))
    )
    (net (code "90") (name "unconnected-(P606-PadMH)") (class "Default")
      (node (ref "P606") (pin "MH") (pinfunction "MH_MH") (pintype "passive"))
    )
    (net (code "91") (name "unconnected-(P607-PadMH)") (class "Default")
      (node (ref "P607") (pin "MH") (pinfunction "MH_MH") (pintype "passive"))
    )
    (net (code "92") (name "unconnected-(SW603-PadNC2)") (class "Default")
      (node (ref "SW603") (pin "NC2") (pinfunction "NC2_NC2") (pintype "passive+no_connect"))
    )
    (net (code "93") (name "unconnected-(SW603-PadNO1)") (class "Default")
      (node (ref "SW603") (pin "NO1") (pinfunction "NO1_NO1") (pintype "passive+no_connect"))
    )
    (net (code "94") (name "unconnected-(SW604-PadNC2)") (class "Default")
      (node (ref "SW604") (pin "NC2") (pinfunction "NC2_NC2") (pintype "passive+no_connect"))
    )
    (net (code "95") (name "unconnected-(SW604-PadNO1)") (class "Default")
      (node (ref "SW604") (pin "NO1") (pinfunction "NO1_NO1") (pintype "passive+no_connect"))
    )
  )
)
